# keyboard.net
KiCad netlist of a schematic drawn in Altium Designer
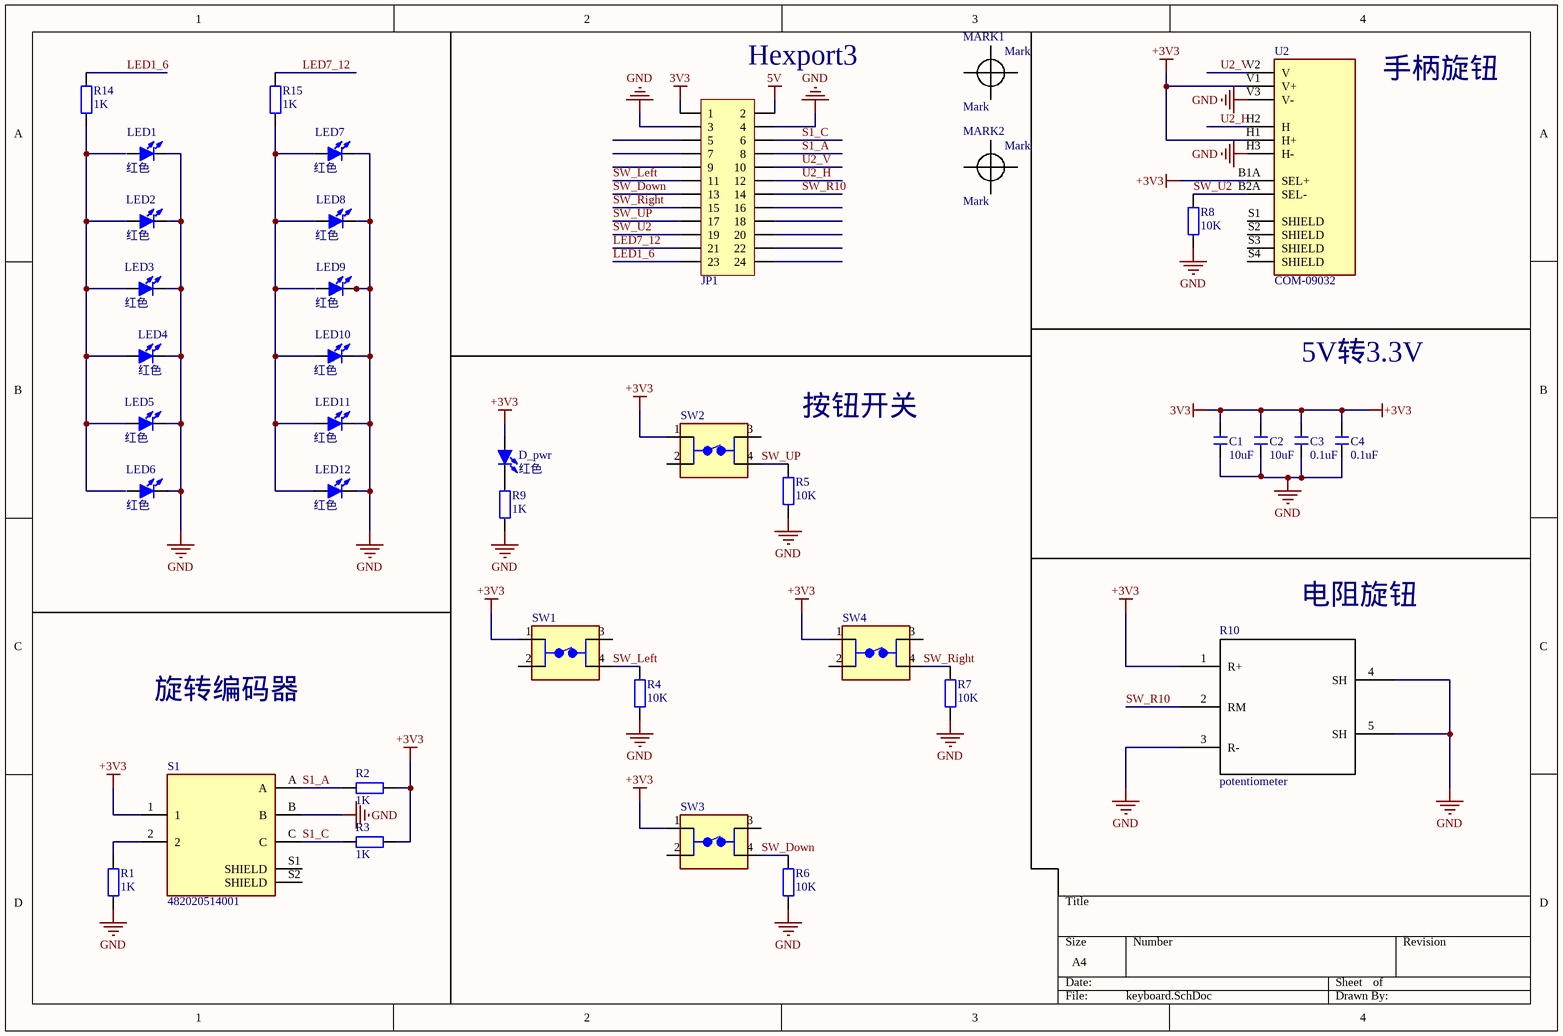
[diagram p0: keyboard.SchDoc]

(export (version "E")
  (design (tool "Eeschema 10.0.6"))
  (components
    (comp (ref "C1")
      (value "10uF")
      (footprint "C 0603_L")
      (description "贴片电容")
      (libsource (lib "0.1 - 电阻-电容-电感") (part "C"))
    )
    (comp (ref "C2")
      (value "10uF")
      (footprint "C 0603_L")
      (description "贴片电容")
      (libsource (lib "0.1 - 电阻-电容-电感") (part "C"))
    )
    (comp (ref "C3")
      (value "0.1uF")
      (footprint "C 0603_L")
      (description "贴片电容")
      (libsource (lib "0.1 - 电阻-电容-电感") (part "C"))
    )
    (comp (ref "C4")
      (value "0.1uF")
      (footprint "C 0603_L")
      (description "贴片电容")
      (libsource (lib "0.1 - 电阻-电容-电感") (part "C"))
    )
    (comp (ref "D_pwr")
      (value "红色")
      (footprint "LED 0603R")
      (description "贴片LED")
      (fields (field (name "版权归属") "封装库来自淘宝 ID：黄晶宝石"))
      (libsource (lib "0.3 - LED发光二极管") (part "LED-SMD"))
    )
    (comp (ref "JP1")
      (value "Header 2X11")
      (footprint "HDR2.54-WI-2x12P")
      (description "12*2P接插件")
      (fields (field (name "版权归属") "封装库来自淘宝卖家 ID：黄晶宝石"))
      (libsource (lib "5.4 - 接插件-脚距2.54 (100mil) ") (part "Header 12X2"))
    )
    (comp (ref "LED1")
      (value "红色")
      (footprint "LED 0603R")
      (description "贴片LED")
      (fields (field (name "版权归属") "封装库来自淘宝 ID：黄晶宝石"))
      (libsource (lib "0.3 - LED发光二极管") (part "LED-SMD"))
    )
    (comp (ref "LED2")
      (value "红色")
      (footprint "LED 0603R")
      (description "贴片LED")
      (fields (field (name "版权归属") "封装库来自淘宝 ID：黄晶宝石"))
      (libsource (lib "0.3 - LED发光二极管") (part "LED-SMD"))
    )
    (comp (ref "LED3")
      (value "红色")
      (footprint "LED 0603R")
      (description "贴片LED")
      (fields (field (name "版权归属") "封装库来自淘宝 ID：黄晶宝石"))
      (libsource (lib "0.3 - LED发光二极管") (part "LED-SMD"))
    )
    (comp (ref "LED4")
      (value "红色")
      (footprint "LED 0603R")
      (description "贴片LED")
      (fields (field (name "版权归属") "封装库来自淘宝 ID：黄晶宝石"))
      (libsource (lib "0.3 - LED发光二极管") (part "LED-SMD"))
    )
    (comp (ref "LED5")
      (value "红色")
      (footprint "LED 0603R")
      (description "贴片LED")
      (fields (field (name "版权归属") "封装库来自淘宝 ID：黄晶宝石"))
      (libsource (lib "0.3 - LED发光二极管") (part "LED-SMD"))
    )
    (comp (ref "LED6")
      (value "红色")
      (footprint "LED 0603R")
      (description "贴片LED")
      (fields (field (name "版权归属") "封装库来自淘宝 ID：黄晶宝石"))
      (libsource (lib "0.3 - LED发光二极管") (part "LED-SMD"))
    )
    (comp (ref "LED7")
      (value "红色")
      (footprint "LED 0603R")
      (description "贴片LED")
      (fields (field (name "版权归属") "封装库来自淘宝 ID：黄晶宝石"))
      (libsource (lib "0.3 - LED发光二极管") (part "LED-SMD"))
    )
    (comp (ref "LED8")
      (value "红色")
      (footprint "LED 0603R")
      (description "贴片LED")
      (fields (field (name "版权归属") "封装库来自淘宝 ID：黄晶宝石"))
      (libsource (lib "0.3 - LED发光二极管") (part "LED-SMD"))
    )
    (comp (ref "LED9")
      (value "红色")
      (footprint "LED 0603R")
      (description "贴片LED")
      (fields (field (name "版权归属") "封装库来自淘宝 ID：黄晶宝石"))
      (libsource (lib "0.3 - LED发光二极管") (part "LED-SMD"))
    )
    (comp (ref "LED10")
      (value "红色")
      (footprint "LED 0603R")
      (description "贴片LED")
      (fields (field (name "版权归属") "封装库来自淘宝 ID：黄晶宝石"))
      (libsource (lib "0.3 - LED发光二极管") (part "LED-SMD"))
    )
    (comp (ref "LED11")
      (value "红色")
      (footprint "LED 0603R")
      (description "贴片LED")
      (fields (field (name "版权归属") "封装库来自淘宝 ID：黄晶宝石"))
      (libsource (lib "0.3 - LED发光二极管") (part "LED-SMD"))
    )
    (comp (ref "LED12")
      (value "红色")
      (footprint "LED 0603R")
      (description "贴片LED")
      (fields (field (name "版权归属") "封装库来自淘宝 ID：黄晶宝石"))
      (libsource (lib "0.3 - LED发光二极管") (part "LED-SMD"))
    )
    (comp (ref "MARK1") (value "Mark") (footprint "Mark:Mark") (libsource (lib "Mark") (part "Mark")))
    (comp (ref "MARK2") (value "Mark") (footprint "Mark:Mark") (libsource (lib "Mark") (part "Mark")))
    (comp (ref "R1")
      (value "1K")
      (footprint "R 0603_L")
      (description "贴片电阻")
      (fields (field (name "版权归属") "来自淘宝 ID：黄晶宝石"))
      (libsource (lib "0.1 - 电阻-电容-电感") (part "R"))
    )
    (comp (ref "R2")
      (value "1K")
      (footprint "R 0603_L")
      (description "贴片电阻")
      (fields (field (name "版权归属") "来自淘宝 ID：黄晶宝石"))
      (libsource (lib "0.1 - 电阻-电容-电感") (part "R"))
    )
    (comp (ref "R3")
      (value "1K")
      (footprint "R 0603_L")
      (description "贴片电阻")
      (fields (field (name "版权归属") "来自淘宝 ID：黄晶宝石"))
      (libsource (lib "0.1 - 电阻-电容-电感") (part "R"))
    )
    (comp (ref "R4")
      (value "10K")
      (footprint "R 0603_L")
      (description "贴片电阻")
      (fields (field (name "版权归属") "来自淘宝 ID：黄晶宝石"))
      (libsource (lib "0.1 - 电阻-电容-电感") (part "R"))
    )
    (comp (ref "R5")
      (value "10K")
      (footprint "R 0603_L")
      (description "贴片电阻")
      (fields (field (name "版权归属") "来自淘宝 ID：黄晶宝石"))
      (libsource (lib "0.1 - 电阻-电容-电感") (part "R"))
    )
    (comp (ref "R6")
      (value "10K")
      (footprint "R 0603_L")
      (description "贴片电阻")
      (fields (field (name "版权归属") "来自淘宝 ID：黄晶宝石"))
      (libsource (lib "0.1 - 电阻-电容-电感") (part "R"))
    )
    (comp (ref "R7")
      (value "10K")
      (footprint "R 0603_L")
      (description "贴片电阻")
      (fields (field (name "版权归属") "来自淘宝 ID：黄晶宝石"))
      (libsource (lib "0.1 - 电阻-电容-电感") (part "R"))
    )
    (comp (ref "R8")
      (value "10K")
      (footprint "R 0603_L")
      (description "贴片电阻")
      (fields (field (name "版权归属") "来自淘宝 ID：黄晶宝石"))
      (libsource (lib "0.1 - 电阻-电容-电感") (part "R"))
    )
    (comp (ref "R9")
      (value "1K")
      (footprint "R 0603_L")
      (description "贴片电阻")
      (fields (field (name "版权归属") "来自淘宝 ID：黄晶宝石"))
      (libsource (lib "0.1 - 电阻-电容-电感") (part "R"))
    )
    (comp (ref "R10")
      (value "potentiometer")
      (footprint "PCBComponent_1 - duplicate")
      (libsource (lib "hexbot_keyboard") (part "R?"))
    )
    (comp (ref "R14")
      (value "1K")
      (footprint "R 0603_L")
      (description "贴片电阻")
      (fields (field (name "版权归属") "来自淘宝 ID：黄晶宝石"))
      (libsource (lib "0.1 - 电阻-电容-电感") (part "R"))
    )
    (comp (ref "R15")
      (value "1K")
      (footprint "R 0603_L")
      (description "贴片电阻")
      (fields (field (name "版权归属") "来自淘宝 ID：黄晶宝石"))
      (libsource (lib "0.1 - 电阻-电容-电感") (part "R"))
    )
    (comp (ref "S1")
      (value "482020514001")
      (footprint "SW_482020514001")
      (description "Rotary Encoder Mechanical 20 Quadrature _Incremental_ Vertical")
      (fields (field (name "MF") "Wurth Electronics"))
      (libsource (lib "hexbot_keyboard") (part "482020514001"))
    )
    (comp (ref "SW1")
      (value "4-1437565-1")
      (footprint "TE_FSM4JSMA")
      (description "Tactile Switch SPST-NO Top Actuated Surface Mount")
      (fields (field (name "MP") "FSM4JSMA") (field (name "MF") "TE Connectivity"))
      (libsource (lib "hexbot_keyboard") (part "FSM4JSMA"))
    )
    (comp (ref "SW2")
      (value "4-1437565-1")
      (footprint "TE_FSM4JSMA")
      (description "Tactile Switch SPST-NO Top Actuated Surface Mount")
      (fields (field (name "MP") "FSM4JSMA") (field (name "MF") "TE Connectivity"))
      (libsource (lib "hexbot_keyboard") (part "FSM4JSMA"))
    )
    (comp (ref "SW3")
      (value "4-1437565-1")
      (footprint "TE_FSM4JSMA")
      (description "Tactile Switch SPST-NO Top Actuated Surface Mount")
      (fields (field (name "MP") "FSM4JSMA") (field (name "MF") "TE Connectivity"))
      (libsource (lib "hexbot_keyboard") (part "FSM4JSMA"))
    )
    (comp (ref "SW4")
      (value "4-1437565-1")
      (footprint "TE_FSM4JSMA")
      (description "Tactile Switch SPST-NO Top Actuated Surface Mount")
      (fields (field (name "MP") "FSM4JSMA") (field (name "MF") "TE Connectivity"))
      (libsource (lib "hexbot_keyboard") (part "FSM4JSMA"))
    )
    (comp (ref "U2")
      (value "COM-09032")
      (footprint "XDCR_COM-09032")
      (description "Joystick, 2 - Axis Analog _Resistive_ Output")
      (fields (field (name "MF") "SparkFun Electronics"))
      (libsource (lib "hexbot_keyboard") (part "COM-09032"))
    )
  )
  (nets
    (net (code "1") (name "+3V3") (class "Default")
      (node (ref "C1") (pin "2") (pinfunction "2_2") (pintype "passive"))
      (node (ref "C2") (pin "2") (pinfunction "2_2") (pintype "passive"))
      (node (ref "C3") (pin "2") (pinfunction "2_2") (pintype "passive"))
      (node (ref "C4") (pin "2") (pinfunction "2_2") (pintype "passive"))
      (node (ref "D_pwr") (pin "1") (pinfunction "A_1") (pintype "passive"))
      (node (ref "JP1") (pin "1") (pinfunction "1_1") (pintype "passive"))
      (node (ref "R10") (pin "1") (pinfunction "R+_1") (pintype "passive"))
      (node (ref "R2") (pin "1") (pinfunction "1_1") (pintype "passive"))
      (node (ref "R3") (pin "1") (pinfunction "1_1") (pintype "passive"))
      (node (ref "S1") (pin "1") (pinfunction "1_1") (pintype "passive"))
      (node (ref "SW1") (pin "1") (pinfunction "1_1") (pintype "passive"))
      (node (ref "SW2") (pin "1") (pinfunction "1_1") (pintype "passive"))
      (node (ref "SW3") (pin "1") (pinfunction "1_1") (pintype "passive"))
      (node (ref "SW4") (pin "1") (pinfunction "1_1") (pintype "passive"))
      (node (ref "U2") (pin "B1A") (pinfunction "SEL+_B1A") (pintype "passive"))
      (node (ref "U2") (pin "H1") (pinfunction "H+_H1") (pintype "passive"))
      (node (ref "U2") (pin "V1") (pinfunction "V+_V1") (pintype "passive"))
    )
    (net (code "2") (name "/LED1_6") (class "Default")
      (node (ref "JP1") (pin "23") (pinfunction "23_23") (pintype "passive"))
      (node (ref "R14") (pin "2") (pinfunction "2_2") (pintype "passive"))
    )
    (net (code "3") (name "/LED7_12") (class "Default")
      (node (ref "JP1") (pin "21") (pinfunction "21_21") (pintype "passive"))
      (node (ref "R15") (pin "2") (pinfunction "2_2") (pintype "passive"))
    )
    (net (code "4") (name "/S1_A") (class "Default")
      (node (ref "JP1") (pin "8") (pinfunction "8_8") (pintype "passive"))
      (node (ref "R2") (pin "2") (pinfunction "2_2") (pintype "passive"))
      (node (ref "S1") (pin "A") (pinfunction "A_A") (pintype "passive"))
    )
    (net (code "5") (name "/S1_C") (class "Default")
      (node (ref "JP1") (pin "6") (pinfunction "6_6") (pintype "passive"))
      (node (ref "R3") (pin "2") (pinfunction "2_2") (pintype "passive"))
      (node (ref "S1") (pin "C") (pinfunction "C_C") (pintype "passive"))
    )
    (net (code "6") (name "/SW_Down") (class "Default")
      (node (ref "JP1") (pin "13") (pinfunction "13_13") (pintype "passive"))
      (node (ref "R6") (pin "2") (pinfunction "2_2") (pintype "passive"))
      (node (ref "SW3") (pin "4") (pinfunction "4_4") (pintype "passive"))
    )
    (net (code "7") (name "/SW_Left") (class "Default")
      (node (ref "JP1") (pin "11") (pinfunction "11_11") (pintype "passive"))
      (node (ref "R4") (pin "2") (pinfunction "2_2") (pintype "passive"))
      (node (ref "SW1") (pin "4") (pinfunction "4_4") (pintype "passive"))
    )
    (net (code "8") (name "/SW_R10") (class "Default")
      (node (ref "JP1") (pin "14") (pinfunction "14_14") (pintype "passive"))
      (node (ref "R10") (pin "2") (pinfunction "RM_2") (pintype "passive"))
    )
    (net (code "9") (name "/SW_Right") (class "Default")
      (node (ref "JP1") (pin "15") (pinfunction "15_15") (pintype "passive"))
      (node (ref "R7") (pin "2") (pinfunction "2_2") (pintype "passive"))
      (node (ref "SW4") (pin "4") (pinfunction "4_4") (pintype "passive"))
    )
    (net (code "10") (name "/SW_U2") (class "Default")
      (node (ref "JP1") (pin "19") (pinfunction "19_19") (pintype "passive"))
      (node (ref "R8") (pin "2") (pinfunction "2_2") (pintype "passive"))
      (node (ref "U2") (pin "B2A") (pinfunction "SEL-_B2A") (pintype "passive"))
    )
    (net (code "11") (name "/SW_UP") (class "Default")
      (node (ref "JP1") (pin "17") (pinfunction "17_17") (pintype "passive"))
      (node (ref "R5") (pin "2") (pinfunction "2_2") (pintype "passive"))
      (node (ref "SW2") (pin "4") (pinfunction "4_4") (pintype "passive"))
    )
    (net (code "12") (name "/U2_H") (class "Default")
      (node (ref "JP1") (pin "12") (pinfunction "12_12") (pintype "passive"))
      (node (ref "U2") (pin "H2") (pinfunction "H_H2") (pintype "passive"))
    )
    (net (code "13") (name "/U2_V") (class "Default")
      (node (ref "JP1") (pin "10") (pinfunction "10_10") (pintype "passive"))
      (node (ref "U2") (pin "V2") (pinfunction "V_V2") (pintype "passive"))
    )
    (net (code "14") (name "5V") (class "Default")
      (node (ref "JP1") (pin "2") (pinfunction "2_2") (pintype "passive"))
    )
    (net (code "15") (name "GND") (class "Default")
      (node (ref "C1") (pin "1") (pinfunction "1_1") (pintype "passive"))
      (node (ref "C2") (pin "1") (pinfunction "1_1") (pintype "passive"))
      (node (ref "C3") (pin "1") (pinfunction "1_1") (pintype "passive"))
      (node (ref "C4") (pin "1") (pinfunction "1_1") (pintype "passive"))
      (node (ref "JP1") (pin "3") (pinfunction "3_3") (pintype "passive"))
      (node (ref "JP1") (pin "4") (pinfunction "4_4") (pintype "passive"))
      (node (ref "LED1") (pin "2") (pinfunction "K_2") (pintype "passive"))
      (node (ref "LED10") (pin "2") (pinfunction "K_2") (pintype "passive"))
      (node (ref "LED11") (pin "2") (pinfunction "K_2") (pintype "passive"))
      (node (ref "LED12") (pin "2") (pinfunction "K_2") (pintype "passive"))
      (node (ref "LED2") (pin "2") (pinfunction "K_2") (pintype "passive"))
      (node (ref "LED3") (pin "2") (pinfunction "K_2") (pintype "passive"))
      (node (ref "LED4") (pin "2") (pinfunction "K_2") (pintype "passive"))
      (node (ref "LED5") (pin "2") (pinfunction "K_2") (pintype "passive"))
      (node (ref "LED6") (pin "2") (pinfunction "K_2") (pintype "passive"))
      (node (ref "LED7") (pin "2") (pinfunction "K_2") (pintype "passive"))
      (node (ref "LED8") (pin "2") (pinfunction "K_2") (pintype "passive"))
      (node (ref "LED9") (pin "2") (pinfunction "K_2") (pintype "passive"))
      (node (ref "R1") (pin "2") (pinfunction "2_2") (pintype "passive"))
      (node (ref "R10") (pin "3") (pinfunction "R-_3") (pintype "passive"))
      (node (ref "R10") (pin "4") (pinfunction "SH_4") (pintype "passive"))
      (node (ref "R10") (pin "5") (pinfunction "SH_5") (pintype "passive"))
      (node (ref "R4") (pin "1") (pinfunction "1_1") (pintype "passive"))
      (node (ref "R5") (pin "1") (pinfunction "1_1") (pintype "passive"))
      (node (ref "R6") (pin "1") (pinfunction "1_1") (pintype "passive"))
      (node (ref "R7") (pin "1") (pinfunction "1_1") (pintype "passive"))
      (node (ref "R8") (pin "1") (pinfunction "1_1") (pintype "passive"))
      (node (ref "R9") (pin "1") (pinfunction "1_1") (pintype "passive"))
      (node (ref "S1") (pin "B") (pinfunction "B_B") (pintype "passive"))
      (node (ref "U2") (pin "H3") (pinfunction "H-_H3") (pintype "passive"))
      (node (ref "U2") (pin "V3") (pinfunction "V-_V3") (pintype "passive"))
    )
    (net (code "16") (name "Net-(D_pwr-K)") (class "Default")
      (node (ref "D_pwr") (pin "2") (pinfunction "K_2") (pintype "passive"))
      (node (ref "R9") (pin "2") (pinfunction "2_2") (pintype "passive"))
    )
    (net (code "17") (name "Net-(LED2-A)") (class "Default")
      (node (ref "LED2") (pin "1") (pinfunction "A_1") (pintype "passive"))
      (node (ref "LED3") (pin "1") (pinfunction "A_1") (pintype "passive"))
      (node (ref "LED4") (pin "1") (pinfunction "A_1") (pintype "passive"))
      (node (ref "LED5") (pin "1") (pinfunction "A_1") (pintype "passive"))
      (node (ref "R14") (pin "1") (pinfunction "1_1") (pintype "passive"))
    )
    (net (code "18") (name "Net-(LED10-A)") (class "Default")
      (node (ref "LED10") (pin "1") (pinfunction "A_1") (pintype "passive"))
      (node (ref "LED11") (pin "1") (pinfunction "A_1") (pintype "passive"))
      (node (ref "LED12") (pin "1") (pinfunction "A_1") (pintype "passive"))
      (node (ref "LED7") (pin "1") (pinfunction "A_1") (pintype "passive"))
      (node (ref "LED8") (pin "1") (pinfunction "A_1") (pintype "passive"))
      (node (ref "R15") (pin "1") (pinfunction "1_1") (pintype "passive"))
    )
    (net (code "19") (name "Net-(R1-Pad1)") (class "Default")
      (node (ref "R1") (pin "1") (pinfunction "1_1") (pintype "passive"))
      (node (ref "S1") (pin "2") (pinfunction "2_2") (pintype "passive"))
    )
    (net (code "20") (name "unconnected-(JP1-Pad5)") (class "Default")
      (node (ref "JP1") (pin "5") (pinfunction "5_5") (pintype "passive"))
    )
    (net (code "21") (name "unconnected-(JP1-Pad7)") (class "Default")
      (node (ref "JP1") (pin "7") (pinfunction "7_7") (pintype "passive"))
    )
    (net (code "22") (name "unconnected-(JP1-Pad9)") (class "Default")
      (node (ref "JP1") (pin "9") (pinfunction "9_9") (pintype "passive"))
    )
    (net (code "23") (name "unconnected-(JP1-Pad16)") (class "Default")
      (node (ref "JP1") (pin "16") (pinfunction "16_16") (pintype "passive"))
    )
    (net (code "24") (name "unconnected-(JP1-Pad18)") (class "Default")
      (node (ref "JP1") (pin "18") (pinfunction "18_18") (pintype "passive"))
    )
    (net (code "25") (name "unconnected-(JP1-Pad20)") (class "Default")
      (node (ref "JP1") (pin "20") (pinfunction "20_20") (pintype "passive"))
    )
    (net (code "26") (name "unconnected-(JP1-Pad22)") (class "Default")
      (node (ref "JP1") (pin "22") (pinfunction "22_22") (pintype "passive"))
    )
    (net (code "27") (name "unconnected-(JP1-Pad24)") (class "Default")
      (node (ref "JP1") (pin "24") (pinfunction "24_24") (pintype "passive"))
    )
    (net (code "28") (name "unconnected-(LED1-A-Pad1)") (class "Default")
      (node (ref "LED1") (pin "1") (pinfunction "A_1") (pintype "passive"))
    )
    (net (code "29") (name "unconnected-(LED6-A-Pad1)") (class "Default")
      (node (ref "LED6") (pin "1") (pinfunction "A_1") (pintype "passive"))
    )
    (net (code "30") (name "unconnected-(LED9-A-Pad1)") (class "Default")
      (node (ref "LED9") (pin "1") (pinfunction "A_1") (pintype "passive"))
    )
    (net (code "31") (name "unconnected-(S1-SHIELD-PadS1)") (class "Default")
      (node (ref "S1") (pin "S1") (pinfunction "SHIELD_S1") (pintype "passive"))
    )
    (net (code "32") (name "unconnected-(S1-SHIELD-PadS2)") (class "Default")
      (node (ref "S1") (pin "S2") (pinfunction "SHIELD_S2") (pintype "passive"))
    )
    (net (code "33") (name "unconnected-(SW1-Pad2)") (class "Default")
      (node (ref "SW1") (pin "2") (pinfunction "2_2") (pintype "passive"))
    )
    (net (code "34") (name "unconnected-(SW1-Pad3)") (class "Default")
      (node (ref "SW1") (pin "3") (pinfunction "3_3") (pintype "passive"))
    )
    (net (code "35") (name "unconnected-(SW2-Pad2)") (class "Default")
      (node (ref "SW2") (pin "2") (pinfunction "2_2") (pintype "passive"))
    )
    (net (code "36") (name "unconnected-(SW2-Pad3)") (class "Default")
      (node (ref "SW2") (pin "3") (pinfunction "3_3") (pintype "passive"))
    )
    (net (code "37") (name "unconnected-(SW3-Pad2)") (class "Default")
      (node (ref "SW3") (pin "2") (pinfunction "2_2") (pintype "passive"))
    )
    (net (code "38") (name "unconnected-(SW3-Pad3)") (class "Default")
      (node (ref "SW3") (pin "3") (pinfunction "3_3") (pintype "passive"))
    )
    (net (code "39") (name "unconnected-(SW4-Pad2)") (class "Default")
      (node (ref "SW4") (pin "2") (pinfunction "2_2") (pintype "passive"))
    )
    (net (code "40") (name "unconnected-(SW4-Pad3)") (class "Default")
      (node (ref "SW4") (pin "3") (pinfunction "3_3") (pintype "passive"))
    )
    (net (code "41") (name "unconnected-(U2-SHIELD-PadS1)") (class "Default")
      (node (ref "U2") (pin "S1") (pinfunction "SHIELD_S1") (pintype "passive"))
    )
    (net (code "42") (name "unconnected-(U2-SHIELD-PadS2)") (class "Default")
      (node (ref "U2") (pin "S2") (pinfunction "SHIELD_S2") (pintype "passive"))
    )
    (net (code "43") (name "unconnected-(U2-SHIELD-PadS3)") (class "Default")
      (node (ref "U2") (pin "S3") (pinfunction "SHIELD_S3") (pintype "passive"))
    )
    (net (code "44") (name "unconnected-(U2-SHIELD-PadS4)") (class "Default")
      (node (ref "U2") (pin "S4") (pinfunction "SHIELD_S4") (pintype "passive"))
    )
  )
)
